# AMU-S19-V00-CURRENT5kWSimulation.net
KiCad netlist of a schematic drawn in Altium Designer
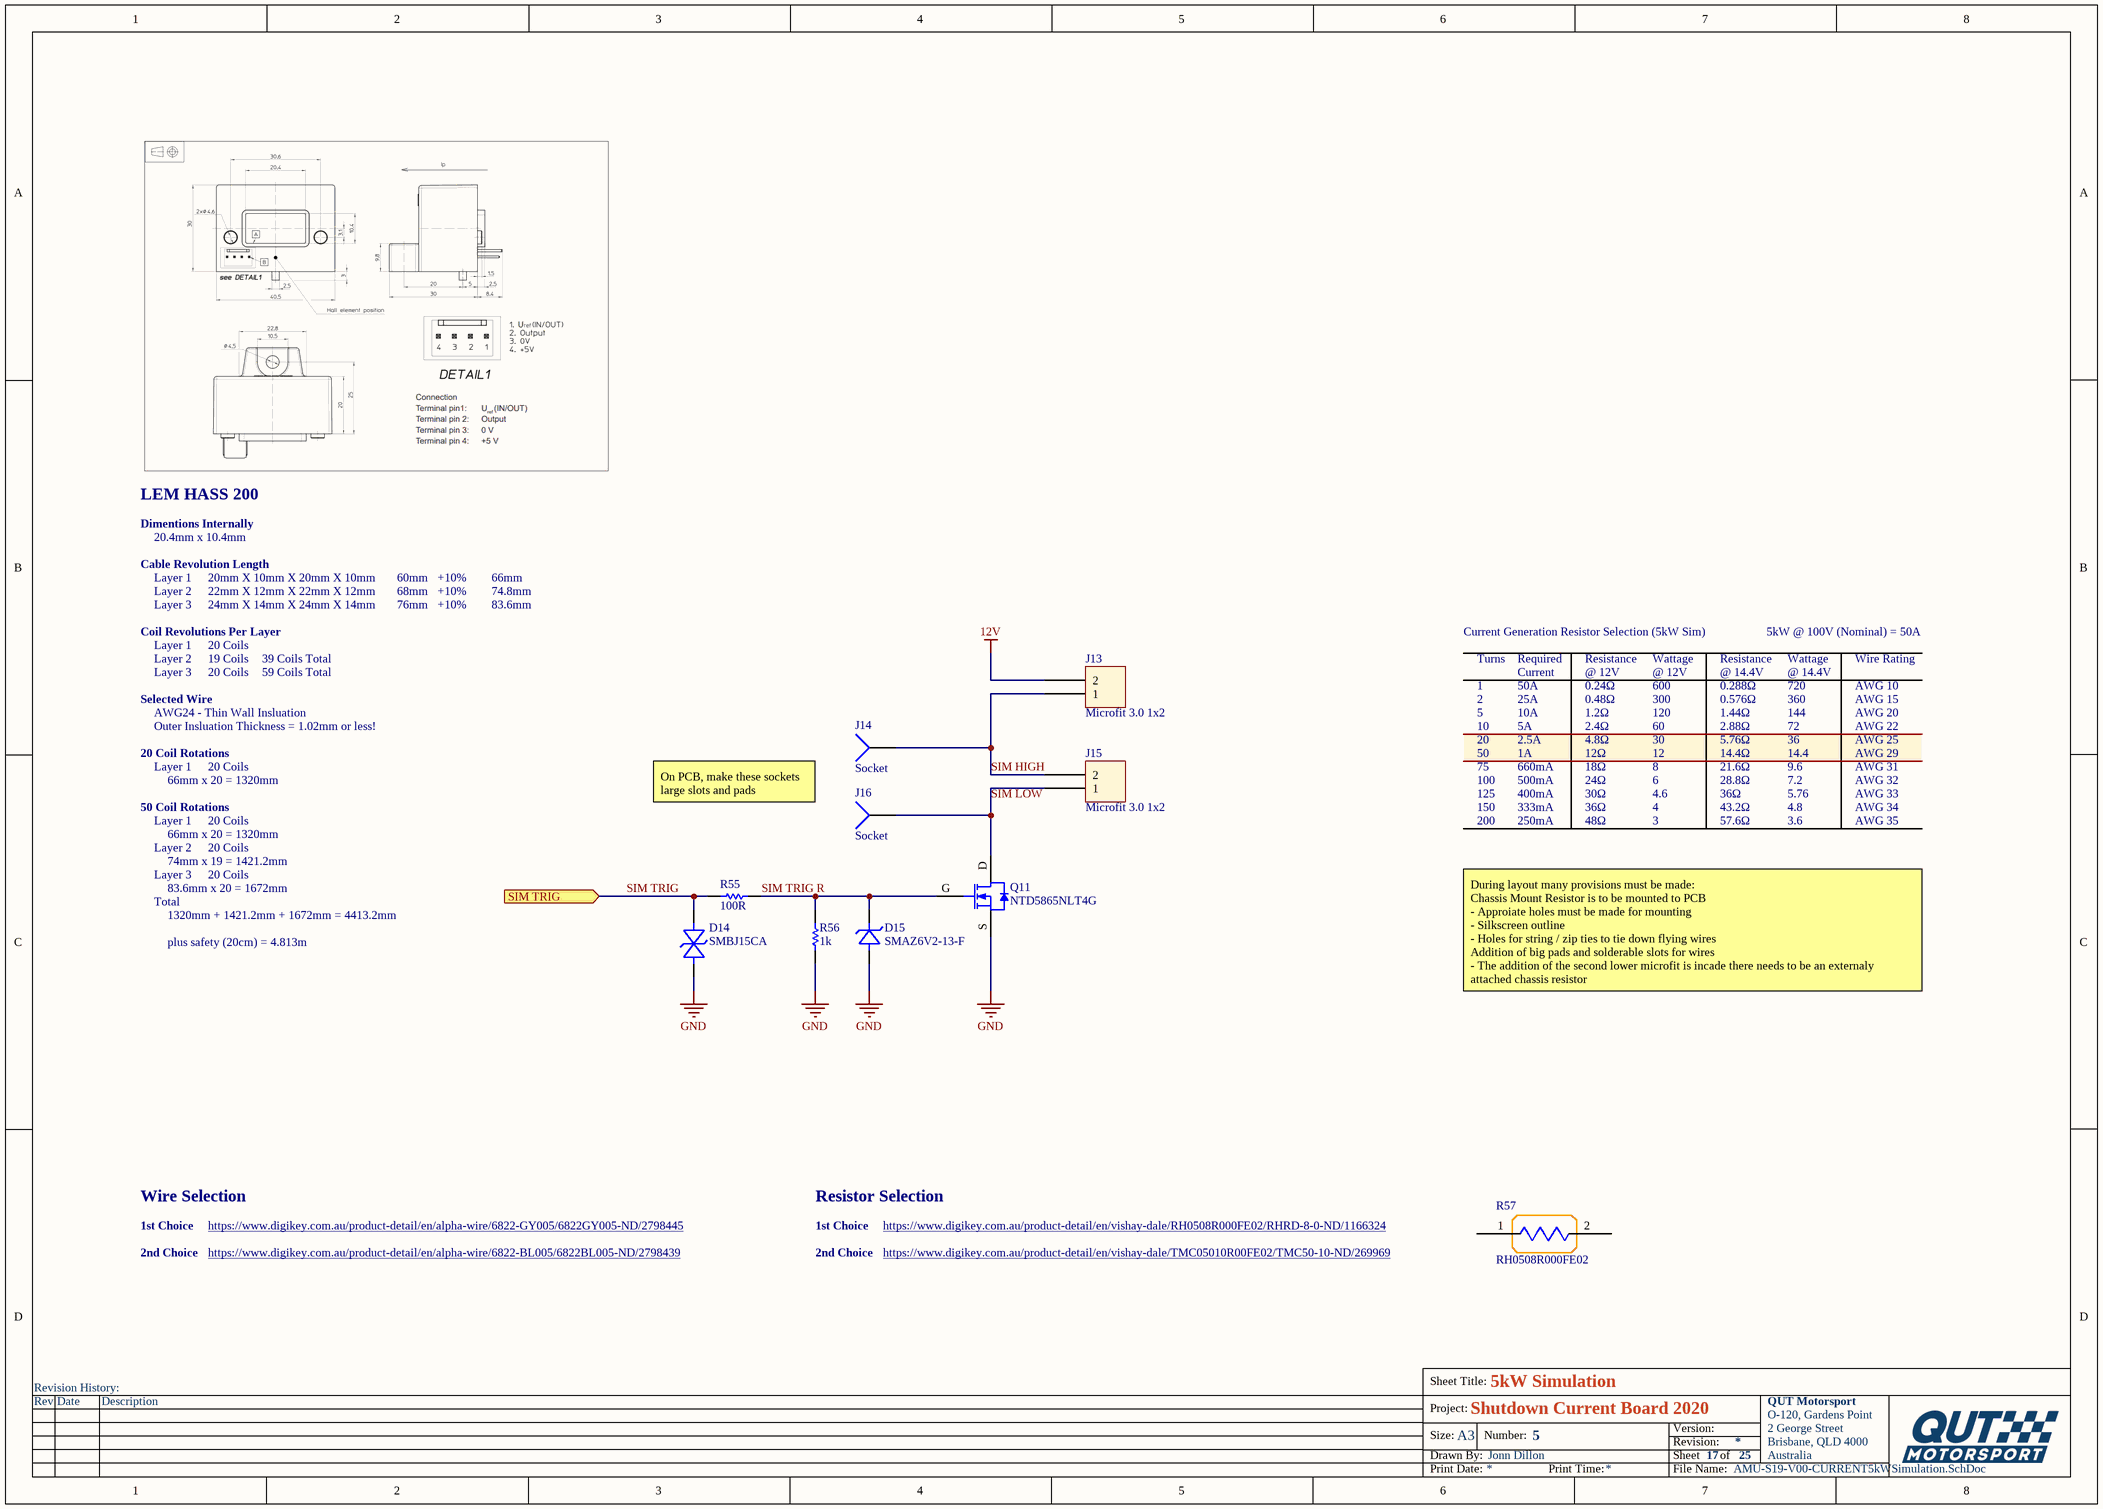
[diagram p0: AMU-S19-V00-CURRENT5kWSimulation.SchDoc]

(export (version "E")
  (design (tool "Eeschema 10.0.6"))
  (components
    (comp (ref "D14")
      (value "SMBJ15CA")
      (footprint "SMB")
      (description "Diode, SMD, TVS Diode, 15V 24.4V, DO214AA/SMB")
      (libsource (lib "QUTMS_DiodeLibrary") (part "SMBJ15CA"))
    )
    (comp (ref "D15")
      (value "SMAZ6V2-13-F")
      (footprint "SMA")
      (description "Zener Diode 6.2V 1W ±5% Surface Mount SMA")
      (fields (field (name "MANUFACTURER") "Generic") (field (name "MPN") "5V6 500mW SMA"))
      (libsource (lib "QUTMS_DiodeLibrary") (part "SMAZ6V2-13-F"))
    )
    (comp (ref "J13")
      (value "Microfit 3.0 1x2")
      (footprint "Microfit_1X2_R_TH")
      (libsource (lib "QUTMS_MicrofitLibrary") (part "Microfit_1x2"))
    )
    (comp (ref "J14")
      (value "Socket")
      (footprint "PIN1")
      (fields (field (name "PUBLISHER") "Altium Limited"))
      (libsource (lib "Miscellaneous Connectors") (part "Socket"))
    )
    (comp (ref "J15")
      (value "Microfit 3.0 1x2")
      (footprint "Microfit_1X2_R_TH")
      (libsource (lib "QUTMS_MicrofitLibrary") (part "Microfit_1x2"))
    )
    (comp (ref "J16")
      (value "Socket")
      (footprint "PIN1")
      (fields (field (name "PUBLISHER") "Altium Limited"))
      (libsource (lib "Miscellaneous Connectors") (part "Socket"))
    )
    (comp (ref "Q11")
      (value "NTD5865NLT4G")
      (footprint "DPAK TO-252")
      (description "NTD5865NLT4G, 60V 46A")
      (libsource (lib "QUTMS_MOSFETLibrary") (part "NTD5865NLT4G"))
    )
    (comp (ref "R55")
      (value "100R")
      (footprint "Res_ThinFilm_0603")
      (description "Resistor, SMD, 100R, 0.1W, 5%, 0603")
      (libsource (lib "StandardResistors") (part "100R 5%, 0603"))
    )
    (comp (ref "R56")
      (value "1k")
      (footprint "Res_ThinFilm_0603")
      (description "Resistor, SMD, 1k, 0.1W, 5%, 0603")
      (libsource (lib "StandardResistors") (part "1k 5% 0603"))
    )
    (comp (ref "R57")
      (value "RH0508R000FE02")
      (footprint "RH0508R000FE02")
      (description "8 Ohms ±1% 50W Wirewound Chassis Mount Resistor")
      (libsource (lib "QUTMS_SpecialResistors") (part "RH0508R000FE02"))
    )
  )
  (nets
    (net (code "1") (name "/SIM HIGH") (class "Default")
      (node (ref "J13") (pin "1") (pinfunction "1_1") (pintype "passive"))
      (node (ref "J14") (pin "1") (pinfunction "1_1") (pintype "passive"))
      (node (ref "J15") (pin "2") (pinfunction "2_2") (pintype "passive"))
    )
    (net (code "2") (name "/SIM LOW") (class "Default")
      (node (ref "J15") (pin "1") (pinfunction "1_1") (pintype "passive"))
      (node (ref "J16") (pin "1") (pinfunction "1_1") (pintype "passive"))
      (node (ref "Q11") (pin "D") (pinfunction "D_D") (pintype "passive"))
    )
    (net (code "3") (name "/SIM TRIG") (class "Default")
      (node (ref "D14") (pin "K") (pinfunction "Cathode_K") (pintype "passive"))
      (node (ref "R55") (pin "1") (pinfunction "1_1") (pintype "passive"))
    )
    (net (code "4") (name "/SIM TRIG R") (class "Default")
      (node (ref "D15") (pin "K") (pinfunction "Cathode_K") (pintype "passive"))
      (node (ref "Q11") (pin "G") (pinfunction "G_G") (pintype "passive"))
      (node (ref "R55") (pin "2") (pinfunction "2_2") (pintype "passive"))
      (node (ref "R56") (pin "2") (pinfunction "2_2") (pintype "passive"))
    )
    (net (code "5") (name "12V") (class "Default")
      (node (ref "J13") (pin "2") (pinfunction "2_2") (pintype "passive"))
    )
    (net (code "6") (name "GND") (class "Default")
      (node (ref "D14") (pin "A") (pinfunction "Anode_A") (pintype "passive"))
      (node (ref "D15") (pin "A") (pinfunction "Anode_A") (pintype "passive"))
      (node (ref "Q11") (pin "S") (pinfunction "S_S") (pintype "passive"))
      (node (ref "R56") (pin "1") (pinfunction "1_1") (pintype "passive"))
    )
    (net (code "7") (name "unconnected-(R57-Pad1)") (class "Default")
      (node (ref "R57") (pin "1") (pinfunction "1_1") (pintype "passive"))
    )
    (net (code "8") (name "unconnected-(R57-Pad2)") (class "Default")
      (node (ref "R57") (pin "2") (pinfunction "2_2") (pintype "passive"))
    )
  )
)
